# TB66.net
KiCad netlist of a schematic drawn in EAGLE
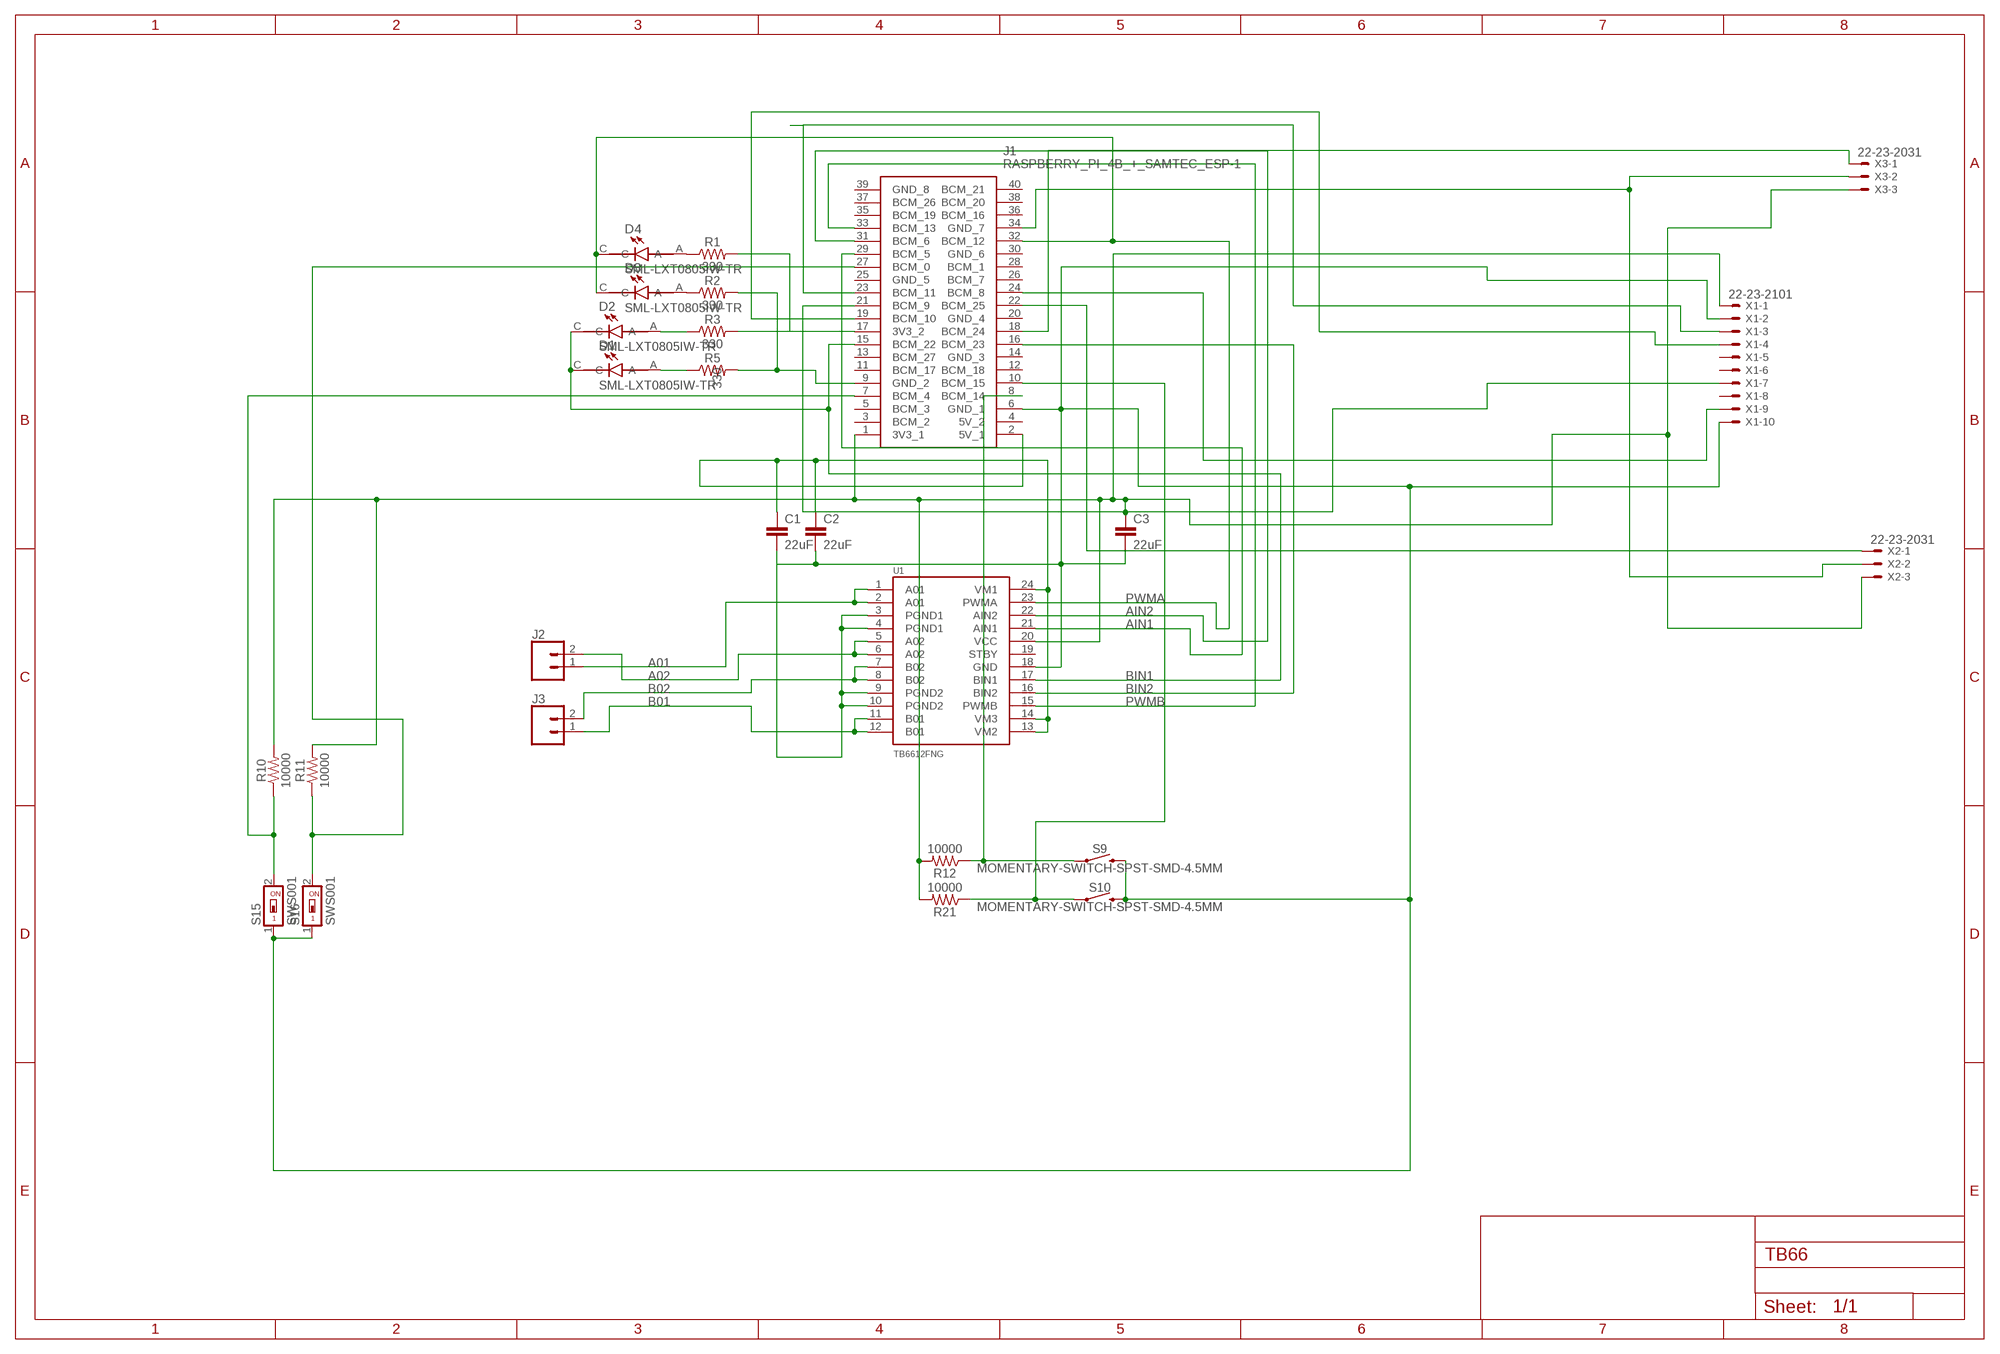
[diagram p0: schematic, sheet 1]

(export (version "E")
  (design (tool "Eeschema 10.0.6"))
  (components
    (comp (ref "C1")
      (value "22uF")
      (footprint "eagle-import:0805")
      (libsource (lib "eagle-import") (part "22UF-0805-6.3V-20%"))
    )
    (comp (ref "C2")
      (value "22uF")
      (footprint "eagle-import:0805")
      (libsource (lib "eagle-import") (part "22UF-0805-6.3V-20%"))
    )
    (comp (ref "C3")
      (value "22uF")
      (footprint "eagle-import:0805")
      (libsource (lib "eagle-import") (part "22UF-0805-6.3V-20%"))
    )
    (comp (ref "D1")
      (value "SML-LXT0805IW-TR")
      (footprint "eagle-import:LEDC2012X120N")
      (fields (field (name "MF") "Lumex Opto/Components"))
      (libsource (lib "eagle-import") (part "SML-LXT0805IW-TR"))
    )
    (comp (ref "D2")
      (value "SML-LXT0805IW-TR")
      (footprint "eagle-import:LEDC2012X120N")
      (fields (field (name "MF") "Lumex Opto/Components"))
      (libsource (lib "eagle-import") (part "SML-LXT0805IW-TR"))
    )
    (comp (ref "D3")
      (value "SML-LXT0805IW-TR")
      (footprint "eagle-import:LEDC2012X120N")
      (fields (field (name "MF") "Lumex Opto/Components"))
      (libsource (lib "eagle-import") (part "SML-LXT0805IW-TR"))
    )
    (comp (ref "D4")
      (value "SML-LXT0805IW-TR")
      (footprint "eagle-import:LEDC2012X120N")
      (fields (field (name "MF") "Lumex Opto/Components"))
      (libsource (lib "eagle-import") (part "SML-LXT0805IW-TR"))
    )
    (comp (ref "J1")
      (value "RASPBERRY_PI_4B_+_SAMTEC_ESP-1")
      (footprint "eagle-import:RASPBERRYPI4B4GB")
      (fields (field (name "MANUFACTURER_PART_NUMBER") "RASPBERRY PI 4B + Samtec ESP-120-33-G-D"))
      (libsource (lib "eagle-import") (part "RASPBERRY_PI_4B_+_SAMTEC_ESP-1"))
    )
    (comp (ref "J2")
      (value "CONN_023.5MM")
      (footprint "eagle-import:SCREWTERMINAL-3.5MM-2")
      (libsource (lib "eagle-import") (part "CONN_023.5MM"))
    )
    (comp (ref "J3")
      (value "CONN_023.5MM")
      (footprint "eagle-import:SCREWTERMINAL-3.5MM-2")
      (libsource (lib "eagle-import") (part "CONN_023.5MM"))
    )
    (comp (ref "R1")
      (value "330")
      (footprint "eagle-import:0805")
      (libsource (lib "eagle-import") (part "RESISTOR0805"))
    )
    (comp (ref "R2")
      (value "330")
      (footprint "eagle-import:0805")
      (libsource (lib "eagle-import") (part "RESISTOR0805"))
    )
    (comp (ref "R3")
      (value "330")
      (footprint "eagle-import:0805")
      (libsource (lib "eagle-import") (part "RESISTOR0805"))
    )
    (comp (ref "R5")
      (value "330")
      (footprint "eagle-import:0805")
      (libsource (lib "eagle-import") (part "RESISTOR0805"))
    )
    (comp (ref "R10")
      (value "10000")
      (footprint "eagle-import:0805")
      (libsource (lib "eagle-import") (part "RESISTOR0805"))
    )
    (comp (ref "R11")
      (value "10000")
      (footprint "eagle-import:0805")
      (libsource (lib "eagle-import") (part "RESISTOR0805"))
    )
    (comp (ref "R12")
      (value "10000")
      (footprint "eagle-import:0805")
      (libsource (lib "eagle-import") (part "RESISTOR0805"))
    )
    (comp (ref "R21")
      (value "10000")
      (footprint "eagle-import:0805")
      (libsource (lib "eagle-import") (part "RESISTOR0805"))
    )
    (comp (ref "S9")
      (value "MOMENTARY-SWITCH-SPST-SMD-4.5MM")
      (footprint "eagle-import:TACTILE_SWITCH_SMD_4.5MM")
      (libsource (lib "eagle-import") (part "MOMENTARY-SWITCH-SPST-SMD-4.5MM"))
    )
    (comp (ref "S10")
      (value "MOMENTARY-SWITCH-SPST-SMD-4.5MM")
      (footprint "eagle-import:TACTILE_SWITCH_SMD_4.5MM")
      (libsource (lib "eagle-import") (part "MOMENTARY-SWITCH-SPST-SMD-4.5MM"))
    )
    (comp (ref "S15")
      (value "SWS001")
      (footprint "eagle-import:SMS-001")
      (libsource (lib "eagle-import") (part "SWS001"))
    )
    (comp (ref "S16")
      (value "SWS001")
      (footprint "eagle-import:SMS-001")
      (libsource (lib "eagle-import") (part "SWS001"))
    )
    (comp (ref "U1")
      (value "TB6612FNG")
      (footprint "eagle-import:SSOP24")
      (libsource (lib "eagle-import") (part "TB6612FNG"))
    )
    (comp (ref "X1")
      (value "22-23-2101")
      (footprint "eagle-import:22-23-2101")
      (fields (field (name "MF") "MOLEX"))
      (libsource (lib "eagle-import") (part "22-23-2101"))
    )
    (comp (ref "X2")
      (value "22-23-2031")
      (footprint "eagle-import:22-23-2031")
      (fields (field (name "MF") "MOLEX"))
      (libsource (lib "eagle-import") (part "22-23-2031"))
    )
    (comp (ref "X3")
      (value "22-23-2031")
      (footprint "eagle-import:22-23-2031")
      (fields (field (name "MF") "MOLEX"))
      (libsource (lib "eagle-import") (part "22-23-2031"))
    )
  )
  (nets
    (net (code "1") (name "/5V_2") (class "Default")
      (node (ref "J1") (pin "4") (pinfunction "5V_2_4") (pintype "power_in"))
    )
    (net (code "2") (name "/A01") (class "Default")
      (node (ref "J2") (pin "1") (pinfunction "1_1") (pintype "passive"))
      (node (ref "U1") (pin "1") (pinfunction "A01_1") (pintype "bidirectional"))
      (node (ref "U1") (pin "2") (pinfunction "A01_2") (pintype "bidirectional"))
    )
    (net (code "3") (name "/A02") (class "Default")
      (node (ref "J2") (pin "2") (pinfunction "2_2") (pintype "passive"))
      (node (ref "U1") (pin "5") (pinfunction "A02_5") (pintype "bidirectional"))
      (node (ref "U1") (pin "6") (pinfunction "A02_6") (pintype "bidirectional"))
    )
    (net (code "4") (name "/AIN1") (class "Default")
      (node (ref "J1") (pin "29") (pinfunction "BCM_5_29") (pintype "bidirectional"))
      (node (ref "U1") (pin "21") (pinfunction "AIN1_21") (pintype "bidirectional"))
    )
    (net (code "5") (name "/AIN2") (class "Default")
      (node (ref "J1") (pin "31") (pinfunction "BCM_6_31") (pintype "bidirectional"))
      (node (ref "U1") (pin "22") (pinfunction "AIN2_22") (pintype "bidirectional"))
    )
    (net (code "6") (name "/B01") (class "Default")
      (node (ref "J3") (pin "1") (pinfunction "1_1") (pintype "passive"))
      (node (ref "U1") (pin "11") (pinfunction "B01_11") (pintype "bidirectional"))
      (node (ref "U1") (pin "12") (pinfunction "B01_12") (pintype "bidirectional"))
    )
    (net (code "7") (name "/B02") (class "Default")
      (node (ref "J3") (pin "2") (pinfunction "2_2") (pintype "passive"))
      (node (ref "U1") (pin "7") (pinfunction "B02_7") (pintype "bidirectional"))
      (node (ref "U1") (pin "8") (pinfunction "B02_8") (pintype "bidirectional"))
    )
    (net (code "8") (name "/BIN1") (class "Default")
      (node (ref "D1") (pin "C") (pinfunction "C_C") (pintype "passive"))
      (node (ref "D2") (pin "C") (pinfunction "C_C") (pintype "passive"))
      (node (ref "J1") (pin "15") (pinfunction "BCM_22_15") (pintype "bidirectional"))
      (node (ref "U1") (pin "17") (pinfunction "BIN1_17") (pintype "bidirectional"))
    )
    (net (code "9") (name "/BIN2") (class "Default")
      (node (ref "J1") (pin "16") (pinfunction "BCM_23_16") (pintype "bidirectional"))
      (node (ref "U1") (pin "16") (pinfunction "BIN2_16") (pintype "bidirectional"))
    )
    (net (code "10") (name "/GND_3") (class "Default")
      (node (ref "J1") (pin "14") (pinfunction "GND_3_14") (pintype "power_in"))
    )
    (net (code "11") (name "/GND_4") (class "Default")
      (node (ref "J1") (pin "20") (pinfunction "GND_4_20") (pintype "power_in"))
    )
    (net (code "12") (name "/GND_5") (class "Default")
      (node (ref "J1") (pin "25") (pinfunction "GND_5_25") (pintype "power_in"))
    )
    (net (code "13") (name "/GND_6") (class "Default")
      (node (ref "J1") (pin "30") (pinfunction "GND_6_30") (pintype "power_in"))
    )
    (net (code "14") (name "/GND_8") (class "Default")
      (node (ref "J1") (pin "39") (pinfunction "GND_8_39") (pintype "power_in"))
    )
    (net (code "15") (name "/PWMA") (class "Default")
      (node (ref "D3") (pin "C") (pinfunction "C_C") (pintype "passive"))
      (node (ref "D4") (pin "C") (pinfunction "C_C") (pintype "passive"))
      (node (ref "J1") (pin "32") (pinfunction "BCM_12_32") (pintype "bidirectional"))
      (node (ref "U1") (pin "23") (pinfunction "PWMA_23") (pintype "bidirectional"))
    )
    (net (code "16") (name "/PWMB") (class "Default")
      (node (ref "J1") (pin "33") (pinfunction "BCM_13_33") (pintype "bidirectional"))
      (node (ref "U1") (pin "15") (pinfunction "PWMB_15") (pintype "bidirectional"))
    )
    (net (code "17") (name "Net-(D1-PadA)") (class "Default")
      (node (ref "D1") (pin "A") (pinfunction "A_A") (pintype "passive"))
      (node (ref "R5") (pin "1") (pinfunction "1_1") (pintype "passive"))
    )
    (net (code "18") (name "Net-(D2-PadA)") (class "Default")
      (node (ref "D2") (pin "A") (pinfunction "A_A") (pintype "passive"))
      (node (ref "R3") (pin "1") (pinfunction "1_1") (pintype "passive"))
    )
    (net (code "19") (name "Net-(D3-PadA)") (class "Default")
      (node (ref "D3") (pin "A") (pinfunction "A_A") (pintype "passive"))
      (node (ref "R2") (pin "1") (pinfunction "1_1") (pintype "passive"))
    )
    (net (code "20") (name "Net-(D4-PadA)") (class "Default")
      (node (ref "D4") (pin "A") (pinfunction "A_A") (pintype "passive"))
      (node (ref "R1") (pin "1") (pinfunction "1_1") (pintype "passive"))
    )
    (net (code "21") (name "Net-(J1-3V3_1)") (class "Default")
      (node (ref "C3") (pin "1") (pinfunction "1_1") (pintype "passive"))
      (node (ref "J1") (pin "1") (pinfunction "3V3_1_1") (pintype "power_in"))
      (node (ref "J1") (pin "21") (pinfunction "BCM_9_21") (pintype "bidirectional"))
      (node (ref "R10") (pin "2") (pinfunction "2_2") (pintype "passive"))
      (node (ref "R11") (pin "2") (pinfunction "2_2") (pintype "passive"))
      (node (ref "R12") (pin "2") (pinfunction "2_2") (pintype "passive"))
      (node (ref "R21") (pin "2") (pinfunction "2_2") (pintype "passive"))
      (node (ref "U1") (pin "20") (pinfunction "VCC_20") (pintype "bidirectional"))
      (node (ref "X1") (pin "1") (pinfunction "S_1") (pintype "passive"))
      (node (ref "X1") (pin "7") (pinfunction "S_7") (pintype "passive"))
      (node (ref "X2") (pin "3") (pinfunction "S_3") (pintype "passive"))
      (node (ref "X3") (pin "3") (pinfunction "S_3") (pintype "passive"))
    )
    (net (code "22") (name "Net-(J1-3V3_2)") (class "Default")
      (node (ref "J1") (pin "17") (pinfunction "3V3_2_17") (pintype "power_in"))
      (node (ref "R1") (pin "2") (pinfunction "2_2") (pintype "passive"))
      (node (ref "R3") (pin "2") (pinfunction "2_2") (pintype "passive"))
    )
    (net (code "23") (name "Net-(J1-5V_1)") (class "Default")
      (node (ref "C1") (pin "1") (pinfunction "1_1") (pintype "passive"))
      (node (ref "C2") (pin "1") (pinfunction "1_1") (pintype "passive"))
      (node (ref "J1") (pin "2") (pinfunction "5V_1_2") (pintype "power_in"))
      (node (ref "U1") (pin "13") (pinfunction "VM2_13") (pintype "bidirectional"))
      (node (ref "U1") (pin "14") (pinfunction "VM3_14") (pintype "bidirectional"))
      (node (ref "U1") (pin "24") (pinfunction "VM1_24") (pintype "bidirectional"))
    )
    (net (code "24") (name "Net-(J1-BCM_0)") (class "Default")
      (node (ref "J1") (pin "27") (pinfunction "BCM_0_27") (pintype "bidirectional"))
      (node (ref "R11") (pin "1") (pinfunction "1_1") (pintype "passive"))
      (node (ref "S16") (pin "2") (pinfunction "2_2") (pintype "passive"))
    )
    (net (code "25") (name "Net-(J1-BCM_4)") (class "Default")
      (node (ref "J1") (pin "7") (pinfunction "BCM_4_7") (pintype "bidirectional"))
      (node (ref "R10") (pin "1") (pinfunction "1_1") (pintype "passive"))
      (node (ref "S15") (pin "2") (pinfunction "2_2") (pintype "passive"))
    )
    (net (code "26") (name "Net-(J1-BCM_8)") (class "Default")
      (node (ref "J1") (pin "24") (pinfunction "BCM_8_24") (pintype "bidirectional"))
      (node (ref "X1") (pin "9") (pinfunction "S_9") (pintype "passive"))
    )
    (net (code "27") (name "Net-(J1-BCM_10)") (class "Default")
      (node (ref "J1") (pin "19") (pinfunction "BCM_10_19") (pintype "bidirectional"))
      (node (ref "X1") (pin "4") (pinfunction "S_4") (pintype "passive"))
    )
    (net (code "28") (name "Net-(J1-BCM_11)") (class "Default")
      (node (ref "J1") (pin "23") (pinfunction "BCM_11_23") (pintype "bidirectional"))
      (node (ref "X1") (pin "3") (pinfunction "S_3") (pintype "passive"))
    )
    (net (code "29") (name "Net-(J1-BCM_14)") (class "Default")
      (node (ref "J1") (pin "8") (pinfunction "BCM_14_8") (pintype "bidirectional"))
      (node (ref "R12") (pin "1") (pinfunction "1_1") (pintype "passive"))
      (node (ref "S9") (pin "2") (pinfunction "1_2") (pintype "passive"))
      (node (ref "S9") (pin "3") (pinfunction "1_3") (pintype "passive"))
    )
    (net (code "30") (name "Net-(J1-BCM_15)") (class "Default")
      (node (ref "J1") (pin "10") (pinfunction "BCM_15_10") (pintype "bidirectional"))
      (node (ref "R21") (pin "1") (pinfunction "1_1") (pintype "passive"))
      (node (ref "S10") (pin "2") (pinfunction "1_2") (pintype "passive"))
      (node (ref "S10") (pin "3") (pinfunction "1_3") (pintype "passive"))
    )
    (net (code "31") (name "Net-(J1-BCM_24)") (class "Default")
      (node (ref "J1") (pin "18") (pinfunction "BCM_24_18") (pintype "bidirectional"))
      (node (ref "X3") (pin "1") (pinfunction "S_1") (pintype "passive"))
    )
    (net (code "32") (name "Net-(J1-BCM_25)") (class "Default")
      (node (ref "J1") (pin "22") (pinfunction "BCM_25_22") (pintype "bidirectional"))
      (node (ref "X2") (pin "1") (pinfunction "S_1") (pintype "passive"))
    )
    (net (code "33") (name "Net-(J1-GND_1)") (class "Default")
      (node (ref "C1") (pin "2") (pinfunction "2_2") (pintype "passive"))
      (node (ref "C2") (pin "2") (pinfunction "2_2") (pintype "passive"))
      (node (ref "C3") (pin "2") (pinfunction "2_2") (pintype "passive"))
      (node (ref "J1") (pin "6") (pinfunction "GND_1_6") (pintype "power_in"))
      (node (ref "S10") (pin "1") (pinfunction "2_1") (pintype "passive"))
      (node (ref "S10") (pin "4") (pinfunction "2_4") (pintype "passive"))
      (node (ref "S15") (pin "1") (pinfunction "1_1") (pintype "passive"))
      (node (ref "S16") (pin "1") (pinfunction "1_1") (pintype "passive"))
      (node (ref "S9") (pin "1") (pinfunction "2_1") (pintype "passive"))
      (node (ref "S9") (pin "4") (pinfunction "2_4") (pintype "passive"))
      (node (ref "U1") (pin "10") (pinfunction "PGND2_10") (pintype "bidirectional"))
      (node (ref "U1") (pin "18") (pinfunction "GND_18") (pintype "bidirectional"))
      (node (ref "U1") (pin "3") (pinfunction "PGND1_3") (pintype "bidirectional"))
      (node (ref "U1") (pin "4") (pinfunction "PGND1_4") (pintype "bidirectional"))
      (node (ref "U1") (pin "9") (pinfunction "PGND2_9") (pintype "bidirectional"))
      (node (ref "X1") (pin "10") (pinfunction "S_10") (pintype "passive"))
      (node (ref "X1") (pin "2") (pinfunction "S_2") (pintype "passive"))
    )
    (net (code "34") (name "Net-(J1-GND_2)") (class "Default")
      (node (ref "J1") (pin "9") (pinfunction "GND_2_9") (pintype "power_in"))
      (node (ref "R2") (pin "2") (pinfunction "2_2") (pintype "passive"))
      (node (ref "R5") (pin "2") (pinfunction "2_2") (pintype "passive"))
    )
    (net (code "35") (name "Net-(J1-GND_7)") (class "Default")
      (node (ref "J1") (pin "34") (pinfunction "GND_7_34") (pintype "power_in"))
      (node (ref "X2") (pin "2") (pinfunction "S_2") (pintype "passive"))
      (node (ref "X3") (pin "2") (pinfunction "S_2") (pintype "passive"))
    )
    (net (code "36") (name "unconnected-(J1-BCM_1-Pad28)") (class "Default")
      (node (ref "J1") (pin "28") (pinfunction "BCM_1_28") (pintype "bidirectional"))
    )
    (net (code "37") (name "unconnected-(J1-BCM_2-Pad3)") (class "Default")
      (node (ref "J1") (pin "3") (pinfunction "BCM_2_3") (pintype "bidirectional"))
    )
    (net (code "38") (name "unconnected-(J1-BCM_3-Pad5)") (class "Default")
      (node (ref "J1") (pin "5") (pinfunction "BCM_3_5") (pintype "bidirectional"))
    )
    (net (code "39") (name "unconnected-(J1-BCM_7-Pad26)") (class "Default")
      (node (ref "J1") (pin "26") (pinfunction "BCM_7_26") (pintype "bidirectional"))
    )
    (net (code "40") (name "unconnected-(J1-BCM_16-Pad36)") (class "Default")
      (node (ref "J1") (pin "36") (pinfunction "BCM_16_36") (pintype "bidirectional"))
    )
    (net (code "41") (name "unconnected-(J1-BCM_17-Pad11)") (class "Default")
      (node (ref "J1") (pin "11") (pinfunction "BCM_17_11") (pintype "bidirectional"))
    )
    (net (code "42") (name "unconnected-(J1-BCM_18-Pad12)") (class "Default")
      (node (ref "J1") (pin "12") (pinfunction "BCM_18_12") (pintype "bidirectional"))
    )
    (net (code "43") (name "unconnected-(J1-BCM_19-Pad35)") (class "Default")
      (node (ref "J1") (pin "35") (pinfunction "BCM_19_35") (pintype "bidirectional"))
    )
    (net (code "44") (name "unconnected-(J1-BCM_20-Pad38)") (class "Default")
      (node (ref "J1") (pin "38") (pinfunction "BCM_20_38") (pintype "bidirectional"))
    )
    (net (code "45") (name "unconnected-(J1-BCM_21-Pad40)") (class "Default")
      (node (ref "J1") (pin "40") (pinfunction "BCM_21_40") (pintype "bidirectional"))
    )
    (net (code "46") (name "unconnected-(J1-BCM_26-Pad37)") (class "Default")
      (node (ref "J1") (pin "37") (pinfunction "BCM_26_37") (pintype "bidirectional"))
    )
    (net (code "47") (name "unconnected-(J1-BCM_27-Pad13)") (class "Default")
      (node (ref "J1") (pin "13") (pinfunction "BCM_27_13") (pintype "bidirectional"))
    )
    (net (code "48") (name "unconnected-(U1-STBY-Pad19)") (class "Default")
      (node (ref "U1") (pin "19") (pinfunction "STBY_19") (pintype "bidirectional"))
    )
    (net (code "49") (name "unconnected-(X1F-S-Pad5)") (class "Default")
      (node (ref "X1") (pin "5") (pinfunction "S_5") (pintype "passive"))
    )
    (net (code "50") (name "unconnected-(X1G-S-Pad6)") (class "Default")
      (node (ref "X1") (pin "6") (pinfunction "S_6") (pintype "passive"))
    )
    (net (code "51") (name "unconnected-(X1I-S-Pad8)") (class "Default")
      (node (ref "X1") (pin "8") (pinfunction "S_8") (pintype "passive"))
    )
  )
)
